# Adafruit_VL6180_Time_of_Flight_Sensor.net
KiCad netlist of a schematic drawn in EAGLE
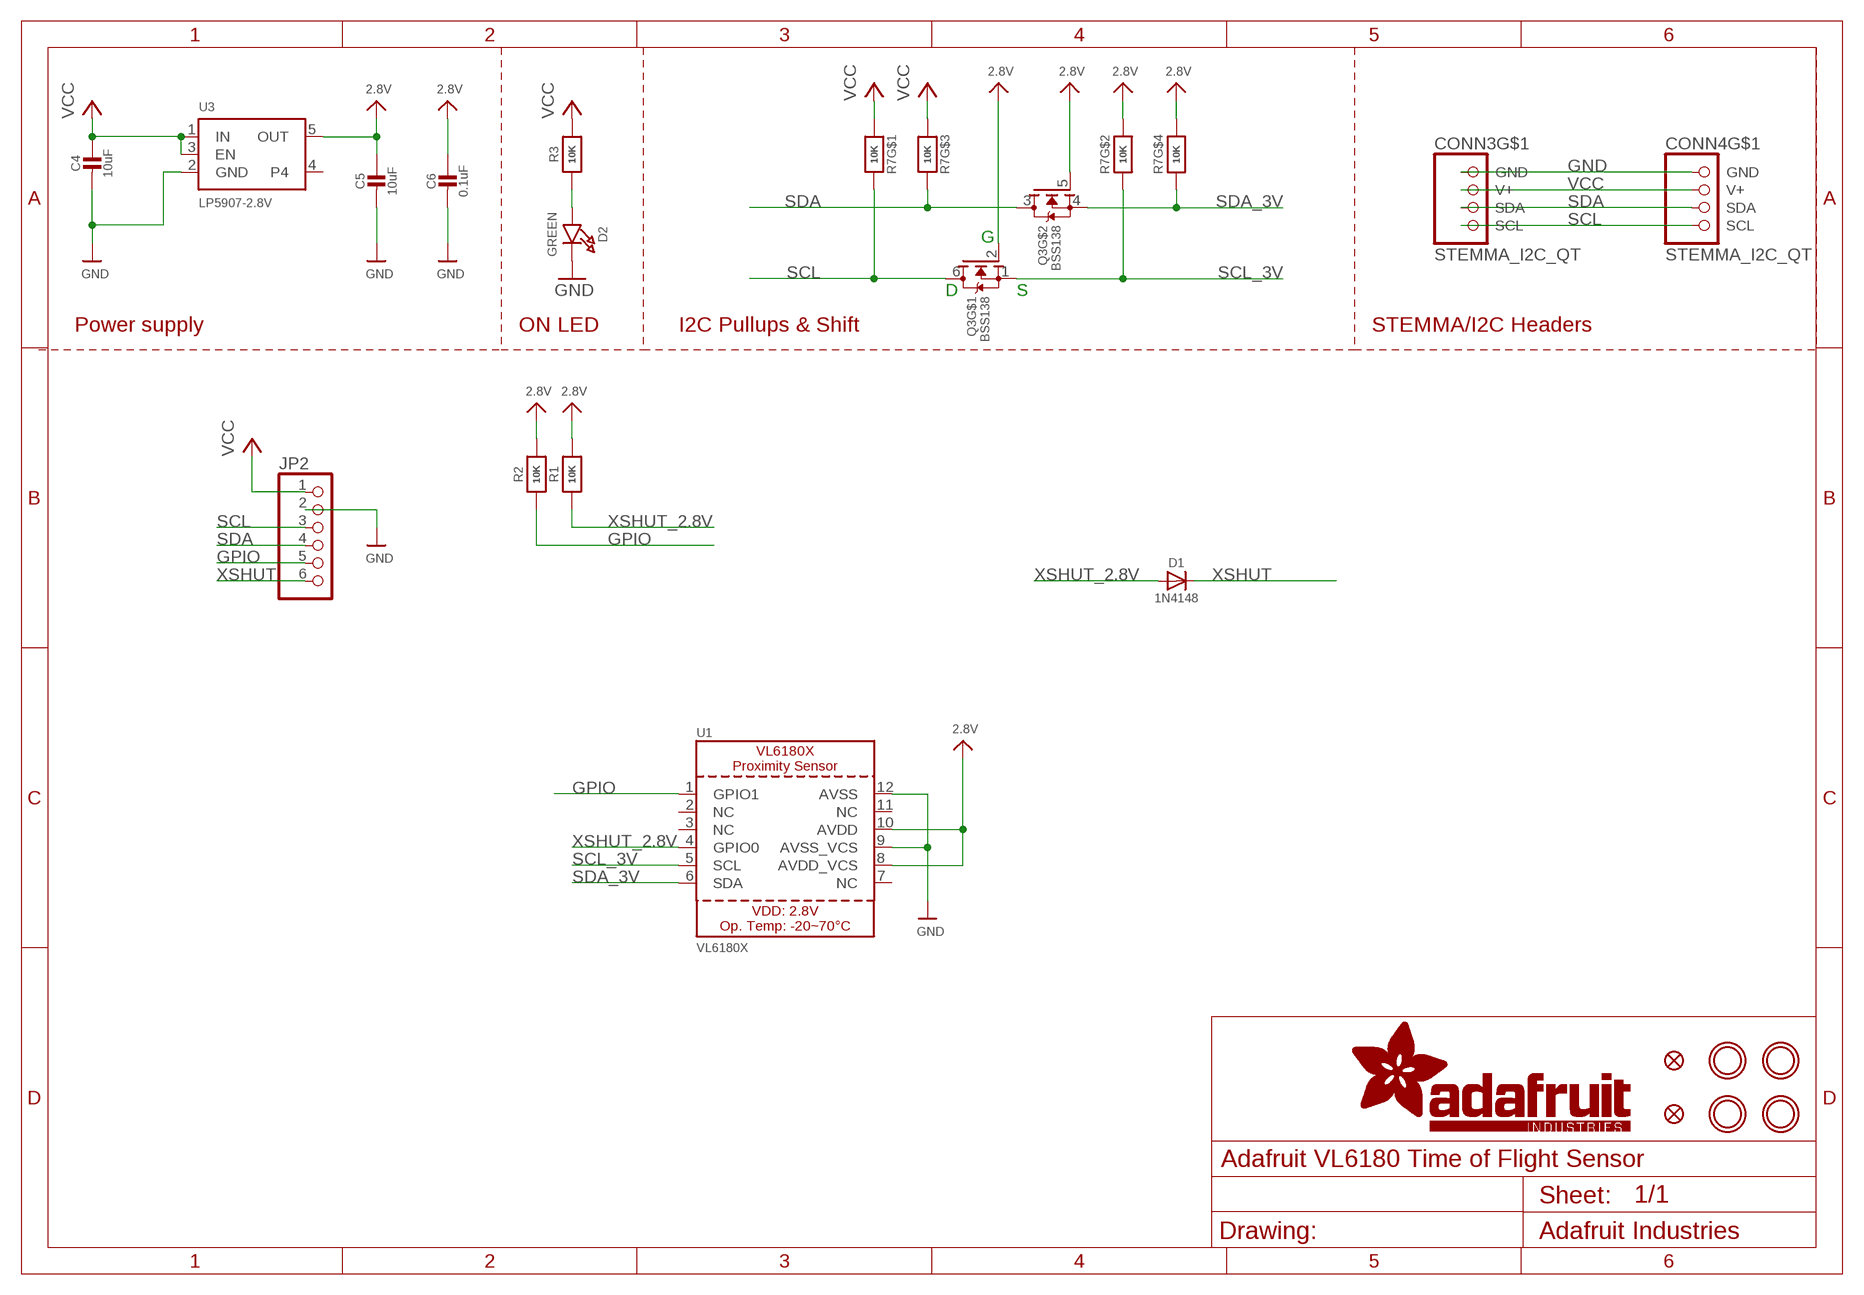
[diagram p0: schematic, sheet 1]

(export (version "E")
  (design (tool "Eeschema 10.0.6"))
  (components
    (comp (ref "C4")
      (value "10uF")
      (footprint "eagle-import:0805-NO")
      (libsource (lib "eagle-import") (part "CAP_CERAMIC0805-NOOUTLINE"))
    )
    (comp (ref "C5")
      (value "10uF")
      (footprint "eagle-import:0805-NO")
      (libsource (lib "eagle-import") (part "CAP_CERAMIC0805-NOOUTLINE"))
    )
    (comp (ref "C6")
      (value "0.1uF")
      (footprint "eagle-import:0603-NO")
      (libsource (lib "eagle-import") (part "CAP_CERAMIC0603_NO"))
    )
    (comp (ref "CONN3")
      (value "STEMMA_I2C_QT")
      (footprint "eagle-import:JST_SH4")
      (libsource (lib "eagle-import") (part "STEMMA_I2C_QT"))
    )
    (comp (ref "CONN4")
      (value "STEMMA_I2C_QT")
      (footprint "eagle-import:JST_SH4")
      (libsource (lib "eagle-import") (part "STEMMA_I2C_QT"))
    )
    (comp (ref "D1")
      (value "1N4148")
      (footprint "eagle-import:SOD-323")
      (libsource (lib "eagle-import") (part "DIODESOD-323"))
    )
    (comp (ref "D2")
      (value "GREEN")
      (footprint "eagle-import:CHIPLED_0603_NOOUTLINE")
      (libsource (lib "eagle-import") (part "LED0603_NOOUTLINE"))
    )
    (comp (ref "FID1")
      (value "FIDUCIAL_1MM")
      (footprint "eagle-import:FIDUCIAL_1MM")
      (libsource (lib "eagle-import") (part "FIDUCIAL_1MM"))
    )
    (comp (ref "FID4")
      (value "FIDUCIAL_1MM")
      (footprint "eagle-import:FIDUCIAL_1MM")
      (libsource (lib "eagle-import") (part "FIDUCIAL_1MM"))
    )
    (comp (ref "JP2")
      (value "HEADER-1X670MIL")
      (footprint "eagle-import:1X06_ROUND_70")
      (libsource (lib "eagle-import") (part "HEADER-1X670MIL"))
    )
    (comp (ref "Q3")
      (value "BSS138")
      (footprint "eagle-import:SOT363")
      (libsource (lib "eagle-import") (part "MOSFET-N_DUAL"))
    )
    (comp (ref "R1")
      (value "10K")
      (footprint "eagle-import:0603-NO")
      (libsource (lib "eagle-import") (part "RESISTOR_0603_NOOUT"))
    )
    (comp (ref "R2")
      (value "10K")
      (footprint "eagle-import:0603-NO")
      (libsource (lib "eagle-import") (part "RESISTOR_0603_NOOUT"))
    )
    (comp (ref "R3")
      (value "10K")
      (footprint "eagle-import:0603-NO")
      (libsource (lib "eagle-import") (part "RESISTOR_0603_NOOUT"))
    )
    (comp (ref "R7")
      (value "10K")
      (footprint "eagle-import:RESPACK_4X0603")
      (libsource (lib "eagle-import") (part "RESISTOR_4PACK"))
    )
    (comp (ref "U$30")
      (value "MOUNTINGHOLE2.5")
      (footprint "eagle-import:MOUNTINGHOLE_2.5_PLATED")
      (libsource (lib "eagle-import") (part "MOUNTINGHOLE2.5"))
    )
    (comp (ref "U$31")
      (value "MOUNTINGHOLE2.5")
      (footprint "eagle-import:MOUNTINGHOLE_2.5_PLATED")
      (libsource (lib "eagle-import") (part "MOUNTINGHOLE2.5"))
    )
    (comp (ref "U$33")
      (value "MOUNTINGHOLE2.5")
      (footprint "eagle-import:MOUNTINGHOLE_2.5_PLATED")
      (libsource (lib "eagle-import") (part "MOUNTINGHOLE2.5"))
    )
    (comp (ref "U$34")
      (value "MOUNTINGHOLE2.5")
      (footprint "eagle-import:MOUNTINGHOLE_2.5_PLATED")
      (libsource (lib "eagle-import") (part "MOUNTINGHOLE2.5"))
    )
    (comp (ref "U1")
      (value "VL6180X")
      (footprint "eagle-import:VL6180")
      (libsource (lib "eagle-import") (part "VL6180X"))
    )
    (comp (ref "U3")
      (value "LP5907-2.8V")
      (footprint "eagle-import:SOT23-5")
      (libsource (lib "eagle-import") (part "VREG_SOT23-5"))
    )
  )
  (nets
    (net (code "1") (name "/GPIO") (class "Default")
      (node (ref "JP2") (pin "5") (pinfunction "5_5") (pintype "passive"))
      (node (ref "R2") (pin "1") (pinfunction "1_1") (pintype "passive"))
      (node (ref "U1") (pin "1") (pinfunction "GPIO1_1") (pintype "bidirectional"))
    )
    (net (code "2") (name "/SCL") (class "Default")
      (node (ref "CONN3") (pin "4") (pinfunction "SCL_4") (pintype "passive"))
      (node (ref "CONN4") (pin "4") (pinfunction "SCL_4") (pintype "passive"))
      (node (ref "JP2") (pin "3") (pinfunction "3_3") (pintype "passive"))
      (node (ref "Q3") (pin "6") (pinfunction "D_6") (pintype "bidirectional"))
      (node (ref "R7") (pin "8") (pinfunction "2_8") (pintype "passive"))
    )
    (net (code "3") (name "/SCL_3V") (class "Default")
      (node (ref "Q3") (pin "1") (pinfunction "S_1") (pintype "bidirectional"))
      (node (ref "R7") (pin "7") (pinfunction "2_7") (pintype "passive"))
      (node (ref "U1") (pin "5") (pinfunction "SCL_5") (pintype "input"))
    )
    (net (code "4") (name "/SDA") (class "Default")
      (node (ref "CONN3") (pin "3") (pinfunction "SDA_3") (pintype "passive"))
      (node (ref "CONN4") (pin "3") (pinfunction "SDA_3") (pintype "passive"))
      (node (ref "JP2") (pin "4") (pinfunction "4_4") (pintype "passive"))
      (node (ref "Q3") (pin "3") (pinfunction "D_3") (pintype "bidirectional"))
      (node (ref "R7") (pin "6") (pinfunction "2_6") (pintype "passive"))
    )
    (net (code "5") (name "/SDA_3V") (class "Default")
      (node (ref "Q3") (pin "4") (pinfunction "S_4") (pintype "bidirectional"))
      (node (ref "R7") (pin "5") (pinfunction "2_5") (pintype "passive"))
      (node (ref "U1") (pin "6") (pinfunction "SDA_6") (pintype "bidirectional"))
    )
    (net (code "6") (name "/XSHUT") (class "Default")
      (node (ref "D1") (pin "C") (pinfunction "C_C") (pintype "passive"))
      (node (ref "JP2") (pin "6") (pinfunction "6_6") (pintype "passive"))
    )
    (net (code "7") (name "/XSHUT_2.8V") (class "Default")
      (node (ref "D1") (pin "A") (pinfunction "A_A") (pintype "passive"))
      (node (ref "R1") (pin "1") (pinfunction "1_1") (pintype "passive"))
      (node (ref "U1") (pin "4") (pinfunction "GPIO0_4") (pintype "bidirectional"))
    )
    (net (code "8") (name "2.8V") (class "Default")
      (node (ref "C5") (pin "1") (pinfunction "1_1") (pintype "passive"))
      (node (ref "C6") (pin "1") (pinfunction "1_1") (pintype "passive"))
      (node (ref "Q3") (pin "2") (pinfunction "G_2") (pintype "bidirectional"))
      (node (ref "Q3") (pin "5") (pinfunction "G_5") (pintype "bidirectional"))
      (node (ref "R1") (pin "2") (pinfunction "2_2") (pintype "passive"))
      (node (ref "R2") (pin "2") (pinfunction "2_2") (pintype "passive"))
      (node (ref "R7") (pin "2") (pinfunction "1_2") (pintype "passive"))
      (node (ref "R7") (pin "4") (pinfunction "1_4") (pintype "passive"))
      (node (ref "U1") (pin "10") (pinfunction "AVDD_10") (pintype "power_in"))
      (node (ref "U1") (pin "8") (pinfunction "AVDD_VCS_8") (pintype "power_in"))
      (node (ref "U3") (pin "5") (pinfunction "OUT_5") (pintype "power_in"))
    )
    (net (code "9") (name "GND") (class "Default")
      (node (ref "C4") (pin "2") (pinfunction "2_2") (pintype "passive"))
      (node (ref "C5") (pin "2") (pinfunction "2_2") (pintype "passive"))
      (node (ref "C6") (pin "2") (pinfunction "2_2") (pintype "passive"))
      (node (ref "CONN3") (pin "1") (pinfunction "GND_1") (pintype "passive"))
      (node (ref "CONN4") (pin "1") (pinfunction "GND_1") (pintype "passive"))
      (node (ref "D2") (pin "C") (pinfunction "C_C") (pintype "passive"))
      (node (ref "JP2") (pin "2") (pinfunction "2_2") (pintype "passive"))
      (node (ref "U1") (pin "12") (pinfunction "AVSS_12") (pintype "power_in"))
      (node (ref "U1") (pin "9") (pinfunction "AVSS_VCS_9") (pintype "power_in"))
      (node (ref "U3") (pin "2") (pinfunction "GND_2") (pintype "power_in"))
    )
    (net (code "10") (name "Net-(D2-PadA)") (class "Default")
      (node (ref "D2") (pin "A") (pinfunction "A_A") (pintype "passive"))
      (node (ref "R3") (pin "1") (pinfunction "1_1") (pintype "passive"))
    )
    (net (code "11") (name "VCC") (class "Default")
      (node (ref "C4") (pin "1") (pinfunction "1_1") (pintype "passive"))
      (node (ref "CONN3") (pin "2") (pinfunction "V+_2") (pintype "passive"))
      (node (ref "CONN4") (pin "2") (pinfunction "V+_2") (pintype "passive"))
      (node (ref "JP2") (pin "1") (pinfunction "1_1") (pintype "passive"))
      (node (ref "R3") (pin "2") (pinfunction "2_2") (pintype "passive"))
      (node (ref "R7") (pin "1") (pinfunction "1_1") (pintype "passive"))
      (node (ref "R7") (pin "3") (pinfunction "1_3") (pintype "passive"))
      (node (ref "U3") (pin "1") (pinfunction "IN_1") (pintype "power_in"))
      (node (ref "U3") (pin "3") (pinfunction "EN_3") (pintype "input"))
    )
    (net (code "12") (name "unconnected-(U1-NC-Pad2)") (class "Default")
      (node (ref "U1") (pin "2") (pinfunction "NC_2") (pintype "no_connect"))
    )
    (net (code "13") (name "unconnected-(U1-NC-Pad3)") (class "Default")
      (node (ref "U1") (pin "3") (pinfunction "NC_3") (pintype "no_connect"))
    )
    (net (code "14") (name "unconnected-(U1-NC-Pad7)") (class "Default")
      (node (ref "U1") (pin "7") (pinfunction "NC_7") (pintype "no_connect"))
    )
    (net (code "15") (name "unconnected-(U1-NC-Pad11)") (class "Default")
      (node (ref "U1") (pin "11") (pinfunction "NC_11") (pintype "no_connect"))
    )
    (net (code "16") (name "unconnected-(U3-P4-Pad4)") (class "Default")
      (node (ref "U3") (pin "4") (pinfunction "P4_4") (pintype "bidirectional"))
    )
  )
)
